# Nucleo_Pb_Buzzer.net
KiCad netlist of a schematic drawn in Altium Designer
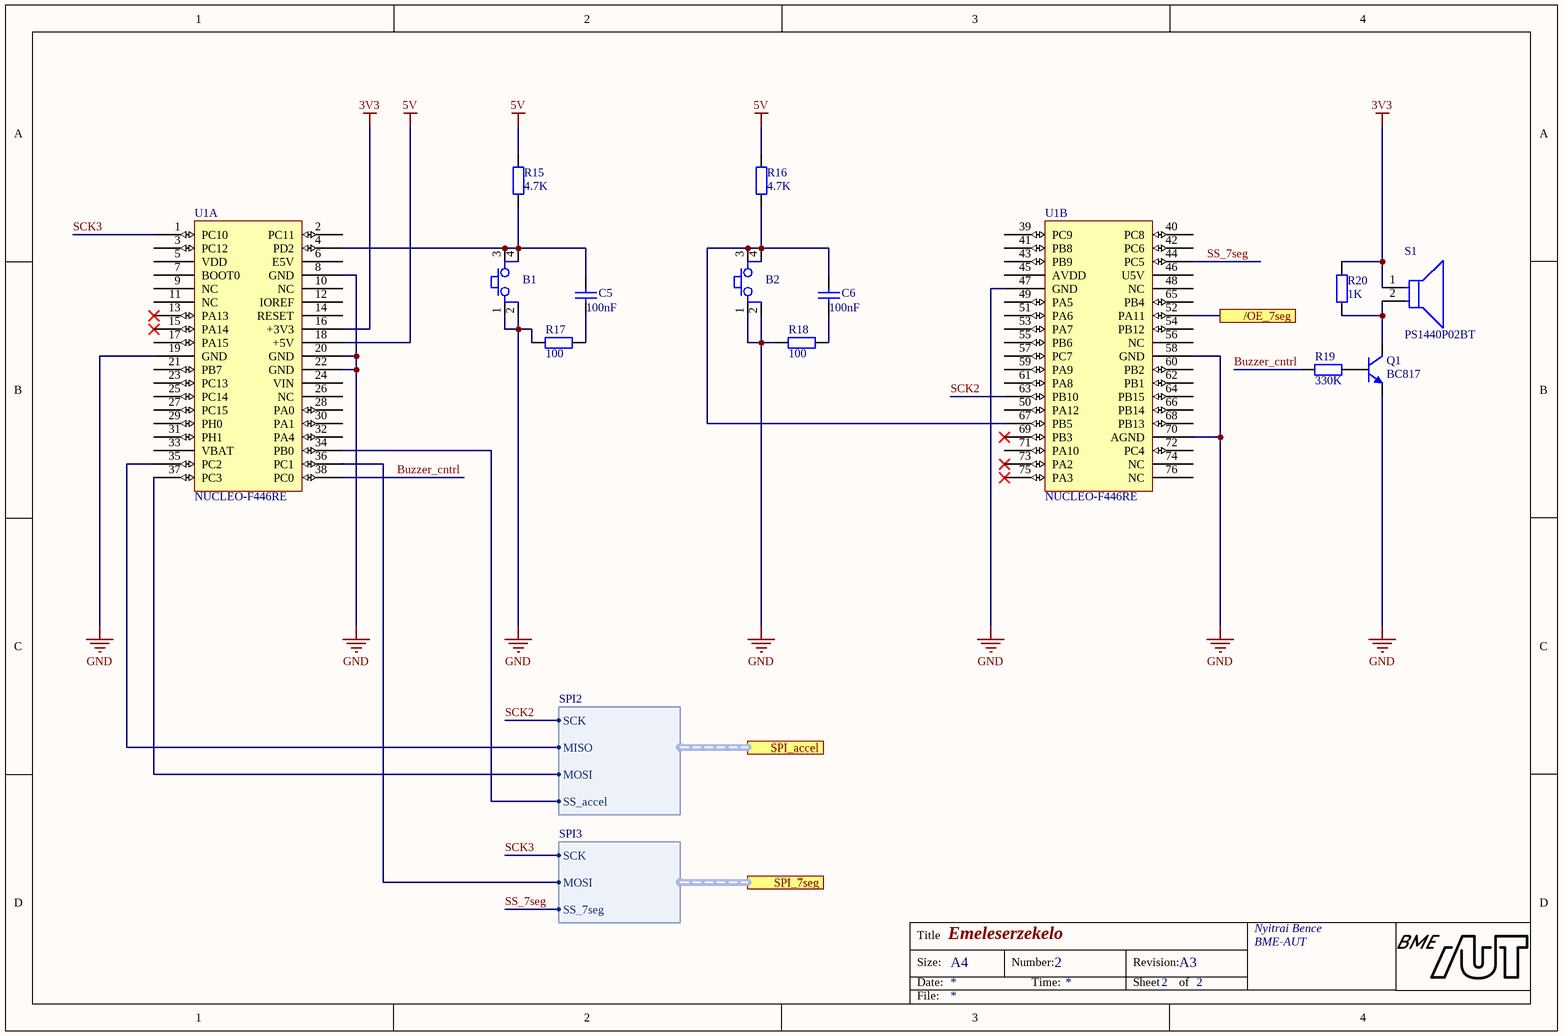
[diagram p0: Nucleo_Pb_Buzzer.SchDoc]

(export (version "E")
  (design (tool "Eeschema 10.0.6"))
  (components
    (comp (ref "B1")
      (value "Button")
      (footprint "FP_BTN_SMD")
      (description "Push button")
      (libsource (lib "hallglib") (part "Button 4P"))
    )
    (comp (ref "B2")
      (value "Button")
      (footprint "FP_BTN_SMD")
      (description "Push button")
      (libsource (lib "hallglib") (part "Button 4P"))
    )
    (comp (ref "C5")
      (value "100nF")
      (footprint "FP_0805_CAP_085")
      (description "Capacitor")
      (libsource (lib "hallglib") (part "CAP"))
    )
    (comp (ref "C6")
      (value "100nF")
      (footprint "FP_0805_CAP_085")
      (description "Capacitor")
      (libsource (lib "hallglib") (part "CAP"))
    )
    (comp (ref "Q1")
      (value "BC817")
      (footprint "FP_SOT23-3")
      (description "NPN General-purpose Transistor")
      (libsource (lib "hallglib") (part "BC817"))
    )
    (comp (ref "R15")
      (value "4.7K")
      (footprint "FP_0805_RES")
      (description "Resistor")
      (fields (field (name "POWER") "125 mW"))
      (libsource (lib "") (part "RES_1"))
    )
    (comp (ref "R16")
      (value "4.7K")
      (footprint "FP_0805_RES")
      (description "Resistor")
      (fields (field (name "POWER") "125 mW"))
      (libsource (lib "") (part "RES_1"))
    )
    (comp (ref "R17")
      (value "100")
      (footprint "FP_0805_RES")
      (description "Resistor")
      (fields (field (name "POWER") "125 mW"))
      (libsource (lib "hallglib") (part "RES"))
    )
    (comp (ref "R18")
      (value "100")
      (footprint "FP_0805_RES")
      (description "Resistor")
      (fields (field (name "POWER") "125 mW"))
      (libsource (lib "hallglib") (part "RES"))
    )
    (comp (ref "R19")
      (value "330K")
      (footprint "FP_0805_RES")
      (description "Resistor")
      (fields (field (name "POWER") "125 mW"))
      (libsource (lib "hallglib") (part "RES"))
    )
    (comp (ref "R20")
      (value "1K")
      (footprint "FP_0805_RES")
      (description "Resistor")
      (fields (field (name "POWER") "125 mW"))
      (libsource (lib "") (part "RES_1"))
    )
    (comp (ref "S1")
      (value "PS1440P02BT")
      (footprint "FP-PS1440P02BT-MFG")
      (description "AUDIO PIEZO TRANSDUCER 30V TH")
      (libsource (lib "hallglib") (part "PS1440P02BT"))
    )
    (comp (ref "U1")
      (value "NUCLEO-F446RE")
      (footprint "FP_NUCLEO-64_2x20")
      (libsource (lib "hallglib") (part "NUCLEO-F446RE"))
    )
  )
  (nets
    (net (code "3") (name "/Buzzer_cntrl") (class "Default")
      (node (ref "R19") (pin "1") (pinfunction "1_1") (pintype "passive"))
      (node (ref "U1") (pin "38") (pinfunction "PC0_38") (pintype "bidirectional"))
    )
    (net (code "4") (name "/MISO") (class "Default")
      (node (ref "U1") (pin "35") (pinfunction "PC2_35") (pintype "bidirectional"))
    )
    (net (code "5") (name "/SCK2") (class "Default")
      (node (ref "U1") (pin "63") (pinfunction "PB10_63") (pintype "bidirectional"))
    )
    (net (code "6") (name "/SCK3") (class "Default")
      (node (ref "U1") (pin "1") (pinfunction "PC10_1") (pintype "bidirectional"))
    )
    (net (code "7") (name "/SS_7seg") (class "Default")
      (node (ref "U1") (pin "44") (pinfunction "PC5_44") (pintype "bidirectional"))
    )
    (net (code "8") (name "/SS_accel") (class "Default")
      (node (ref "U1") (pin "34") (pinfunction "PB0_34") (pintype "bidirectional"))
    )
    (net (code "11") (name "/{slash}OE_7seg") (class "Default")
      (node (ref "U1") (pin "52") (pinfunction "PA11_52") (pintype "bidirectional"))
    )
    (net (code "12") (name "3V3") (class "Default")
      (node (ref "R20") (pin "2") (pinfunction "2_2") (pintype "passive"))
      (node (ref "S1") (pin "1") (pinfunction "1_1") (pintype "passive"))
      (node (ref "U1") (pin "16") (pinfunction "+3V3_16") (pintype "power_in"))
    )
    (net (code "13") (name "5V") (class "Default")
      (node (ref "R15") (pin "2") (pinfunction "2_2") (pintype "passive"))
      (node (ref "R16") (pin "2") (pinfunction "2_2") (pintype "passive"))
      (node (ref "U1") (pin "18") (pinfunction "+5V_18") (pintype "power_in"))
    )
    (net (code "14") (name "GND") (class "Default")
      (node (ref "B1") (pin "1") (pinfunction "1_1") (pintype "passive"))
      (node (ref "B1") (pin "2") (pinfunction "2_2") (pintype "passive"))
      (node (ref "B2") (pin "1") (pinfunction "1_1") (pintype "passive"))
      (node (ref "B2") (pin "2") (pinfunction "2_2") (pintype "passive"))
      (node (ref "Q1") (pin "2") (pinfunction "E_2") (pintype "passive"))
      (node (ref "R17") (pin "1") (pinfunction "1_1") (pintype "passive"))
      (node (ref "R18") (pin "1") (pinfunction "1_1") (pintype "passive"))
      (node (ref "U1") (pin "19") (pinfunction "GND_19") (pintype "passive"))
      (node (ref "U1") (pin "20") (pinfunction "GND_20") (pintype "passive"))
      (node (ref "U1") (pin "22") (pinfunction "GND_22") (pintype "passive"))
      (node (ref "U1") (pin "47") (pinfunction "GND_47") (pintype "passive"))
      (node (ref "U1") (pin "58") (pinfunction "GND_58") (pintype "passive"))
      (node (ref "U1") (pin "70") (pinfunction "AGND_70") (pintype "passive"))
      (node (ref "U1") (pin "8") (pinfunction "GND_8") (pintype "passive"))
    )
    (net (code "15") (name "Net-(C5-Pad1)") (class "Default")
      (node (ref "C5") (pin "1") (pinfunction "1_1") (pintype "passive"))
      (node (ref "R17") (pin "2") (pinfunction "2_2") (pintype "passive"))
    )
    (net (code "16") (name "Net-(C6-Pad1)") (class "Default")
      (node (ref "C6") (pin "1") (pinfunction "1_1") (pintype "passive"))
      (node (ref "R18") (pin "2") (pinfunction "2_2") (pintype "passive"))
    )
    (net (code "17") (name "Net-(Q1-B)") (class "Default")
      (node (ref "Q1") (pin "1") (pinfunction "B_1") (pintype "passive"))
      (node (ref "R19") (pin "2") (pinfunction "2_2") (pintype "passive"))
    )
    (net (code "18") (name "Net-(Q1-C)") (class "Default")
      (node (ref "Q1") (pin "3") (pinfunction "C_3") (pintype "passive"))
      (node (ref "R20") (pin "1") (pinfunction "1_1") (pintype "passive"))
      (node (ref "S1") (pin "2") (pinfunction "2_2") (pintype "passive"))
    )
    (net (code "19") (name "Net-(U1A-PD2)") (class "Default")
      (node (ref "B1") (pin "3") (pinfunction "3_3") (pintype "passive"))
      (node (ref "B1") (pin "4") (pinfunction "4_4") (pintype "passive"))
      (node (ref "C5") (pin "2") (pinfunction "2_2") (pintype "passive"))
      (node (ref "R15") (pin "1") (pinfunction "1_1") (pintype "passive"))
      (node (ref "U1") (pin "4") (pinfunction "PD2_4") (pintype "bidirectional"))
    )
    (net (code "20") (name "Net-(U1B-PB5)") (class "Default")
      (node (ref "B2") (pin "3") (pinfunction "3_3") (pintype "passive"))
      (node (ref "B2") (pin "4") (pinfunction "4_4") (pintype "passive"))
      (node (ref "C6") (pin "2") (pinfunction "2_2") (pintype "passive"))
      (node (ref "R16") (pin "1") (pinfunction "1_1") (pintype "passive"))
      (node (ref "U1") (pin "67") (pinfunction "PB5_67") (pintype "bidirectional"))
    )
    (net (code "21") (name "unconnected-(U1A-BOOT0-Pad7)") (class "Default")
      (node (ref "U1") (pin "7") (pinfunction "BOOT0_7") (pintype "passive"))
    )
    (net (code "22") (name "unconnected-(U1A-E5V-Pad6)") (class "Default")
      (node (ref "U1") (pin "6") (pinfunction "E5V_6") (pintype "power_in"))
    )
    (net (code "23") (name "unconnected-(U1A-IOREF-Pad12)") (class "Default")
      (node (ref "U1") (pin "12") (pinfunction "IOREF_12") (pintype "passive"))
    )
    (net (code "24") (name "unconnected-(U1A-NC-Pad9)") (class "Default")
      (node (ref "U1") (pin "9") (pinfunction "NC_9") (pintype "passive"))
    )
    (net (code "25") (name "unconnected-(U1A-NC-Pad10)") (class "Default")
      (node (ref "U1") (pin "10") (pinfunction "NC_10") (pintype "passive"))
    )
    (net (code "26") (name "unconnected-(U1A-NC-Pad11)") (class "Default")
      (node (ref "U1") (pin "11") (pinfunction "NC_11") (pintype "passive"))
    )
    (net (code "27") (name "unconnected-(U1A-NC-Pad26)") (class "Default")
      (node (ref "U1") (pin "26") (pinfunction "NC_26") (pintype "passive"))
    )
    (net (code "28") (name "unconnected-(U1A-PA0-Pad28)") (class "Default")
      (node (ref "U1") (pin "28") (pinfunction "PA0_28") (pintype "bidirectional"))
    )
    (net (code "29") (name "unconnected-(U1A-PA1-Pad30)") (class "Default")
      (node (ref "U1") (pin "30") (pinfunction "PA1_30") (pintype "bidirectional"))
    )
    (net (code "30") (name "unconnected-(U1A-PA4-Pad32)") (class "Default")
      (node (ref "U1") (pin "32") (pinfunction "PA4_32") (pintype "bidirectional"))
    )
    (net (code "31") (name "unconnected-(U1A-PA13-Pad13)") (class "Default")
      (node (ref "U1") (pin "13") (pinfunction "PA13_13") (pintype "bidirectional+no_connect"))
    )
    (net (code "32") (name "unconnected-(U1A-PA14-Pad15)") (class "Default")
      (node (ref "U1") (pin "15") (pinfunction "PA14_15") (pintype "bidirectional+no_connect"))
    )
    (net (code "33") (name "unconnected-(U1A-PA15-Pad17)") (class "Default")
      (node (ref "U1") (pin "17") (pinfunction "PA15_17") (pintype "bidirectional"))
    )
    (net (code "34") (name "unconnected-(U1A-PB7-Pad21)") (class "Default")
      (node (ref "U1") (pin "21") (pinfunction "PB7_21") (pintype "bidirectional"))
    )
    (net (code "35") (name "unconnected-(U1A-PC1-Pad36)") (class "Default")
      (node (ref "U1") (pin "36") (pinfunction "PC1_36") (pintype "bidirectional"))
    )
    (net (code "36") (name "unconnected-(U1A-PC3-Pad37)") (class "Default")
      (node (ref "U1") (pin "37") (pinfunction "PC3_37") (pintype "bidirectional"))
    )
    (net (code "37") (name "unconnected-(U1A-PC11-Pad2)") (class "Default")
      (node (ref "U1") (pin "2") (pinfunction "PC11_2") (pintype "bidirectional"))
    )
    (net (code "38") (name "unconnected-(U1A-PC12-Pad3)") (class "Default")
      (node (ref "U1") (pin "3") (pinfunction "PC12_3") (pintype "bidirectional"))
    )
    (net (code "39") (name "unconnected-(U1A-PC13-Pad23)") (class "Default")
      (node (ref "U1") (pin "23") (pinfunction "PC13_23") (pintype "bidirectional"))
    )
    (net (code "40") (name "unconnected-(U1A-PC14-Pad25)") (class "Default")
      (node (ref "U1") (pin "25") (pinfunction "PC14_25") (pintype "bidirectional"))
    )
    (net (code "41") (name "unconnected-(U1A-PC15-Pad27)") (class "Default")
      (node (ref "U1") (pin "27") (pinfunction "PC15_27") (pintype "bidirectional"))
    )
    (net (code "42") (name "unconnected-(U1A-PH0-Pad29)") (class "Default")
      (node (ref "U1") (pin "29") (pinfunction "PH0_29") (pintype "bidirectional"))
    )
    (net (code "43") (name "unconnected-(U1A-PH1-Pad31)") (class "Default")
      (node (ref "U1") (pin "31") (pinfunction "PH1_31") (pintype "bidirectional"))
    )
    (net (code "44") (name "unconnected-(U1A-RESET-Pad14)") (class "Default")
      (node (ref "U1") (pin "14") (pinfunction "RESET_14") (pintype "passive"))
    )
    (net (code "45") (name "unconnected-(U1A-VBAT-Pad33)") (class "Default")
      (node (ref "U1") (pin "33") (pinfunction "VBAT_33") (pintype "power_in"))
    )
    (net (code "46") (name "unconnected-(U1A-VDD-Pad5)") (class "Default")
      (node (ref "U1") (pin "5") (pinfunction "VDD_5") (pintype "power_in"))
    )
    (net (code "47") (name "unconnected-(U1A-VIN-Pad24)") (class "Default")
      (node (ref "U1") (pin "24") (pinfunction "VIN_24") (pintype "power_in"))
    )
    (net (code "48") (name "unconnected-(U1B-AVDD-Pad45)") (class "Default")
      (node (ref "U1") (pin "45") (pinfunction "AVDD_45") (pintype "power_in"))
    )
    (net (code "49") (name "unconnected-(U1B-NC-Pad48)") (class "Default")
      (node (ref "U1") (pin "48") (pinfunction "NC_48") (pintype "passive"))
    )
    (net (code "50") (name "unconnected-(U1B-NC-Pad56)") (class "Default")
      (node (ref "U1") (pin "56") (pinfunction "NC_56") (pintype "passive"))
    )
    (net (code "51") (name "unconnected-(U1B-NC-Pad74)") (class "Default")
      (node (ref "U1") (pin "74") (pinfunction "NC_74") (pintype "passive"))
    )
    (net (code "52") (name "unconnected-(U1B-NC-Pad76)") (class "Default")
      (node (ref "U1") (pin "76") (pinfunction "NC_76") (pintype "passive"))
    )
    (net (code "53") (name "unconnected-(U1B-PA2-Pad73)") (class "Default")
      (node (ref "U1") (pin "73") (pinfunction "PA2_73") (pintype "bidirectional+no_connect"))
    )
    (net (code "54") (name "unconnected-(U1B-PA3-Pad75)") (class "Default")
      (node (ref "U1") (pin "75") (pinfunction "PA3_75") (pintype "bidirectional+no_connect"))
    )
    (net (code "55") (name "unconnected-(U1B-PA5-Pad49)") (class "Default")
      (node (ref "U1") (pin "49") (pinfunction "PA5_49") (pintype "bidirectional"))
    )
    (net (code "56") (name "unconnected-(U1B-PA6-Pad51)") (class "Default")
      (node (ref "U1") (pin "51") (pinfunction "PA6_51") (pintype "bidirectional"))
    )
    (net (code "57") (name "unconnected-(U1B-PA7-Pad53)") (class "Default")
      (node (ref "U1") (pin "53") (pinfunction "PA7_53") (pintype "bidirectional"))
    )
    (net (code "58") (name "unconnected-(U1B-PA8-Pad61)") (class "Default")
      (node (ref "U1") (pin "61") (pinfunction "PA8_61") (pintype "bidirectional"))
    )
    (net (code "59") (name "unconnected-(U1B-PA9-Pad59)") (class "Default")
      (node (ref "U1") (pin "59") (pinfunction "PA9_59") (pintype "bidirectional"))
    )
    (net (code "60") (name "unconnected-(U1B-PA10-Pad71)") (class "Default")
      (node (ref "U1") (pin "71") (pinfunction "PA10_71") (pintype "bidirectional"))
    )
    (net (code "61") (name "unconnected-(U1B-PA12-Pad50)") (class "Default")
      (node (ref "U1") (pin "50") (pinfunction "PA12_50") (pintype "bidirectional"))
    )
    (net (code "62") (name "unconnected-(U1B-PB1-Pad62)") (class "Default")
      (node (ref "U1") (pin "62") (pinfunction "PB1_62") (pintype "bidirectional"))
    )
    (net (code "63") (name "unconnected-(U1B-PB2-Pad60)") (class "Default")
      (node (ref "U1") (pin "60") (pinfunction "PB2_60") (pintype "bidirectional"))
    )
    (net (code "64") (name "unconnected-(U1B-PB3-Pad69)") (class "Default")
      (node (ref "U1") (pin "69") (pinfunction "PB3_69") (pintype "bidirectional+no_connect"))
    )
    (net (code "65") (name "unconnected-(U1B-PB4-Pad65)") (class "Default")
      (node (ref "U1") (pin "65") (pinfunction "PB4_65") (pintype "bidirectional"))
    )
    (net (code "66") (name "unconnected-(U1B-PB6-Pad55)") (class "Default")
      (node (ref "U1") (pin "55") (pinfunction "PB6_55") (pintype "bidirectional"))
    )
    (net (code "67") (name "unconnected-(U1B-PB8-Pad41)") (class "Default")
      (node (ref "U1") (pin "41") (pinfunction "PB8_41") (pintype "bidirectional"))
    )
    (net (code "68") (name "unconnected-(U1B-PB9-Pad43)") (class "Default")
      (node (ref "U1") (pin "43") (pinfunction "PB9_43") (pintype "bidirectional"))
    )
    (net (code "69") (name "unconnected-(U1B-PB12-Pad54)") (class "Default")
      (node (ref "U1") (pin "54") (pinfunction "PB12_54") (pintype "bidirectional"))
    )
    (net (code "70") (name "unconnected-(U1B-PB13-Pad68)") (class "Default")
      (node (ref "U1") (pin "68") (pinfunction "PB13_68") (pintype "bidirectional"))
    )
    (net (code "71") (name "unconnected-(U1B-PB14-Pad66)") (class "Default")
      (node (ref "U1") (pin "66") (pinfunction "PB14_66") (pintype "bidirectional"))
    )
    (net (code "72") (name "unconnected-(U1B-PB15-Pad64)") (class "Default")
      (node (ref "U1") (pin "64") (pinfunction "PB15_64") (pintype "bidirectional"))
    )
    (net (code "73") (name "unconnected-(U1B-PC4-Pad72)") (class "Default")
      (node (ref "U1") (pin "72") (pinfunction "PC4_72") (pintype "bidirectional"))
    )
    (net (code "74") (name "unconnected-(U1B-PC6-Pad42)") (class "Default")
      (node (ref "U1") (pin "42") (pinfunction "PC6_42") (pintype "bidirectional"))
    )
    (net (code "75") (name "unconnected-(U1B-PC7-Pad57)") (class "Default")
      (node (ref "U1") (pin "57") (pinfunction "PC7_57") (pintype "bidirectional"))
    )
    (net (code "76") (name "unconnected-(U1B-PC8-Pad40)") (class "Default")
      (node (ref "U1") (pin "40") (pinfunction "PC8_40") (pintype "bidirectional"))
    )
    (net (code "77") (name "unconnected-(U1B-PC9-Pad39)") (class "Default")
      (node (ref "U1") (pin "39") (pinfunction "PC9_39") (pintype "bidirectional"))
    )
    (net (code "78") (name "unconnected-(U1B-U5V-Pad46)") (class "Default")
      (node (ref "U1") (pin "46") (pinfunction "U5V_46") (pintype "power_in"))
    )
  )
)
